# connectors.net
KiCad netlist of a schematic drawn in Altium Designer
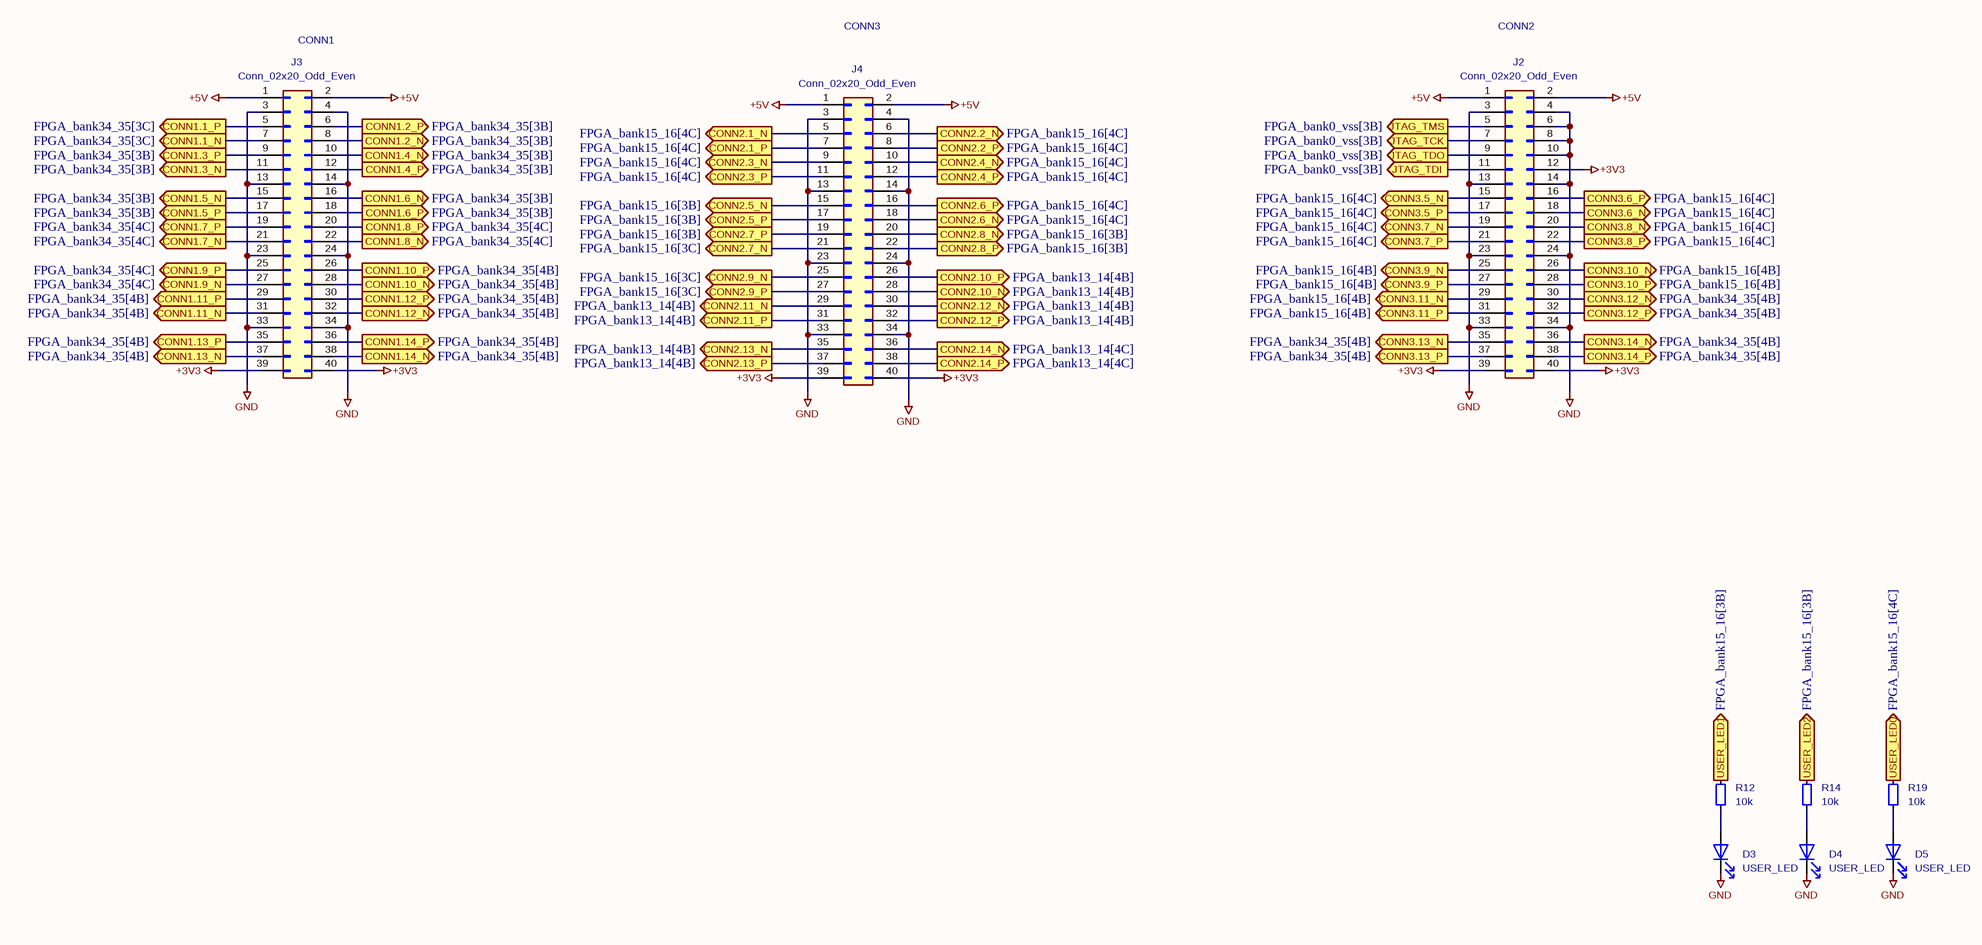
[diagram p0: connectors.SchDoc]

(export (version "E")
  (design (tool "Eeschema 10.0.6"))
  (components
    (comp (ref "D3") (value "USER_LED") (libsource (lib "Device") (part "LED")))
    (comp (ref "D4") (value "USER_LED") (libsource (lib "Device") (part "LED")))
    (comp (ref "D5") (value "USER_LED") (libsource (lib "Device") (part "LED")))
    (comp (ref "J2")
      (value "Conn_02x20_Odd_Even")
      (libsource (lib "Connector_Generic") (part "Conn_02x20_Odd_Even"))
    )
    (comp (ref "J3")
      (value "Conn_02x20_Odd_Even")
      (libsource (lib "Connector_Generic") (part "Conn_02x20_Odd_Even"))
    )
    (comp (ref "J4")
      (value "Conn_02x20_Odd_Even")
      (libsource (lib "Connector_Generic") (part "Conn_02x20_Odd_Even"))
    )
    (comp (ref "R12") (value "10k") (libsource (lib "Device") (part "R_Small")))
    (comp (ref "R14") (value "10k") (libsource (lib "Device") (part "R_Small")))
    (comp (ref "R19") (value "10k") (libsource (lib "Device") (part "R_Small")))
  )
  (nets
    (net (code "1") (name "+3V3") (class "Default")
      (node (ref "J2") (pin "12") (pinfunction "Pin_12_12") (pintype "passive"))
      (node (ref "J2") (pin "39") (pinfunction "Pin_39_39") (pintype "passive"))
      (node (ref "J2") (pin "40") (pinfunction "Pin_40_40") (pintype "passive"))
      (node (ref "J3") (pin "39") (pinfunction "Pin_39_39") (pintype "passive"))
      (node (ref "J3") (pin "40") (pinfunction "Pin_40_40") (pintype "passive"))
      (node (ref "J4") (pin "39") (pinfunction "Pin_39_39") (pintype "passive"))
      (node (ref "J4") (pin "40") (pinfunction "Pin_40_40") (pintype "passive"))
    )
    (net (code "2") (name "+5V") (class "Default")
      (node (ref "J2") (pin "1") (pinfunction "Pin_1_1") (pintype "passive"))
      (node (ref "J2") (pin "2") (pinfunction "Pin_2_2") (pintype "passive"))
      (node (ref "J3") (pin "1") (pinfunction "Pin_1_1") (pintype "passive"))
      (node (ref "J3") (pin "2") (pinfunction "Pin_2_2") (pintype "passive"))
      (node (ref "J4") (pin "1") (pinfunction "Pin_1_1") (pintype "passive"))
      (node (ref "J4") (pin "2") (pinfunction "Pin_2_2") (pintype "passive"))
    )
    (net (code "3") (name "/CONN1.1_N") (class "Default")
      (node (ref "J3") (pin "7") (pinfunction "Pin_7_7") (pintype "passive"))
    )
    (net (code "4") (name "/CONN1.1_P") (class "Default")
      (node (ref "J3") (pin "5") (pinfunction "Pin_5_5") (pintype "passive"))
    )
    (net (code "5") (name "/CONN1.2_N") (class "Default")
      (node (ref "J3") (pin "8") (pinfunction "Pin_8_8") (pintype "passive"))
    )
    (net (code "6") (name "/CONN1.2_P") (class "Default")
      (node (ref "J3") (pin "6") (pinfunction "Pin_6_6") (pintype "passive"))
    )
    (net (code "7") (name "/CONN1.3_N") (class "Default")
      (node (ref "J3") (pin "11") (pinfunction "Pin_11_11") (pintype "passive"))
    )
    (net (code "8") (name "/CONN1.3_P") (class "Default")
      (node (ref "J3") (pin "9") (pinfunction "Pin_9_9") (pintype "passive"))
    )
    (net (code "9") (name "/CONN1.4_N") (class "Default")
      (node (ref "J3") (pin "10") (pinfunction "Pin_10_10") (pintype "passive"))
    )
    (net (code "10") (name "/CONN1.4_P") (class "Default")
      (node (ref "J3") (pin "12") (pinfunction "Pin_12_12") (pintype "passive"))
    )
    (net (code "11") (name "/CONN1.5_N") (class "Default")
      (node (ref "J3") (pin "15") (pinfunction "Pin_15_15") (pintype "passive"))
    )
    (net (code "12") (name "/CONN1.5_P") (class "Default")
      (node (ref "J3") (pin "17") (pinfunction "Pin_17_17") (pintype "passive"))
    )
    (net (code "13") (name "/CONN1.6_N") (class "Default")
      (node (ref "J3") (pin "16") (pinfunction "Pin_16_16") (pintype "passive"))
    )
    (net (code "14") (name "/CONN1.6_P") (class "Default")
      (node (ref "J3") (pin "18") (pinfunction "Pin_18_18") (pintype "passive"))
    )
    (net (code "15") (name "/CONN1.7_N") (class "Default")
      (node (ref "J3") (pin "21") (pinfunction "Pin_21_21") (pintype "passive"))
    )
    (net (code "16") (name "/CONN1.7_P") (class "Default")
      (node (ref "J3") (pin "19") (pinfunction "Pin_19_19") (pintype "passive"))
    )
    (net (code "17") (name "/CONN1.8_N") (class "Default")
      (node (ref "J3") (pin "22") (pinfunction "Pin_22_22") (pintype "passive"))
    )
    (net (code "18") (name "/CONN1.8_P") (class "Default")
      (node (ref "J3") (pin "20") (pinfunction "Pin_20_20") (pintype "passive"))
    )
    (net (code "19") (name "/CONN1.9_N") (class "Default")
      (node (ref "J3") (pin "27") (pinfunction "Pin_27_27") (pintype "passive"))
    )
    (net (code "20") (name "/CONN1.9_P") (class "Default")
      (node (ref "J3") (pin "25") (pinfunction "Pin_25_25") (pintype "passive"))
    )
    (net (code "21") (name "/CONN1.10_N") (class "Default")
      (node (ref "J3") (pin "28") (pinfunction "Pin_28_28") (pintype "passive"))
    )
    (net (code "22") (name "/CONN1.10_P") (class "Default")
      (node (ref "J3") (pin "26") (pinfunction "Pin_26_26") (pintype "passive"))
    )
    (net (code "23") (name "/CONN1.11_N") (class "Default")
      (node (ref "J3") (pin "31") (pinfunction "Pin_31_31") (pintype "passive"))
    )
    (net (code "24") (name "/CONN1.11_P") (class "Default")
      (node (ref "J3") (pin "29") (pinfunction "Pin_29_29") (pintype "passive"))
    )
    (net (code "25") (name "/CONN1.12_N") (class "Default")
      (node (ref "J3") (pin "32") (pinfunction "Pin_32_32") (pintype "passive"))
    )
    (net (code "26") (name "/CONN1.12_P") (class "Default")
      (node (ref "J3") (pin "30") (pinfunction "Pin_30_30") (pintype "passive"))
    )
    (net (code "27") (name "/CONN1.13_N") (class "Default")
      (node (ref "J3") (pin "37") (pinfunction "Pin_37_37") (pintype "passive"))
    )
    (net (code "28") (name "/CONN1.13_P") (class "Default")
      (node (ref "J3") (pin "35") (pinfunction "Pin_35_35") (pintype "passive"))
    )
    (net (code "29") (name "/CONN1.14_N") (class "Default")
      (node (ref "J3") (pin "38") (pinfunction "Pin_38_38") (pintype "passive"))
    )
    (net (code "30") (name "/CONN1.14_P") (class "Default")
      (node (ref "J3") (pin "36") (pinfunction "Pin_36_36") (pintype "passive"))
    )
    (net (code "31") (name "/CONN2.1_N") (class "Default")
      (node (ref "J4") (pin "5") (pinfunction "Pin_5_5") (pintype "passive"))
    )
    (net (code "32") (name "/CONN2.1_P") (class "Default")
      (node (ref "J4") (pin "7") (pinfunction "Pin_7_7") (pintype "passive"))
    )
    (net (code "33") (name "/CONN2.2_N") (class "Default")
      (node (ref "J4") (pin "6") (pinfunction "Pin_6_6") (pintype "passive"))
    )
    (net (code "34") (name "/CONN2.2_P") (class "Default")
      (node (ref "J4") (pin "8") (pinfunction "Pin_8_8") (pintype "passive"))
    )
    (net (code "35") (name "/CONN2.3_N") (class "Default")
      (node (ref "J4") (pin "9") (pinfunction "Pin_9_9") (pintype "passive"))
    )
    (net (code "36") (name "/CONN2.3_P") (class "Default")
      (node (ref "J4") (pin "11") (pinfunction "Pin_11_11") (pintype "passive"))
    )
    (net (code "37") (name "/CONN2.4_N") (class "Default")
      (node (ref "J4") (pin "10") (pinfunction "Pin_10_10") (pintype "passive"))
    )
    (net (code "38") (name "/CONN2.4_P") (class "Default")
      (node (ref "J4") (pin "12") (pinfunction "Pin_12_12") (pintype "passive"))
    )
    (net (code "39") (name "/CONN2.5_N") (class "Default")
      (node (ref "J4") (pin "15") (pinfunction "Pin_15_15") (pintype "passive"))
    )
    (net (code "40") (name "/CONN2.5_P") (class "Default")
      (node (ref "J4") (pin "17") (pinfunction "Pin_17_17") (pintype "passive"))
    )
    (net (code "41") (name "/CONN2.6_N") (class "Default")
      (node (ref "J4") (pin "18") (pinfunction "Pin_18_18") (pintype "passive"))
    )
    (net (code "42") (name "/CONN2.6_P") (class "Default")
      (node (ref "J4") (pin "16") (pinfunction "Pin_16_16") (pintype "passive"))
    )
    (net (code "43") (name "/CONN2.7_N") (class "Default")
      (node (ref "J4") (pin "21") (pinfunction "Pin_21_21") (pintype "passive"))
    )
    (net (code "44") (name "/CONN2.7_P") (class "Default")
      (node (ref "J4") (pin "19") (pinfunction "Pin_19_19") (pintype "passive"))
    )
    (net (code "45") (name "/CONN2.8_N") (class "Default")
      (node (ref "J4") (pin "20") (pinfunction "Pin_20_20") (pintype "passive"))
    )
    (net (code "46") (name "/CONN2.8_P") (class "Default")
      (node (ref "J4") (pin "22") (pinfunction "Pin_22_22") (pintype "passive"))
    )
    (net (code "47") (name "/CONN2.9_N") (class "Default")
      (node (ref "J4") (pin "25") (pinfunction "Pin_25_25") (pintype "passive"))
    )
    (net (code "48") (name "/CONN2.9_P") (class "Default")
      (node (ref "J4") (pin "27") (pinfunction "Pin_27_27") (pintype "passive"))
    )
    (net (code "49") (name "/CONN2.10_N") (class "Default")
      (node (ref "J4") (pin "28") (pinfunction "Pin_28_28") (pintype "passive"))
    )
    (net (code "50") (name "/CONN2.10_P") (class "Default")
      (node (ref "J4") (pin "26") (pinfunction "Pin_26_26") (pintype "passive"))
    )
    (net (code "51") (name "/CONN2.11_N") (class "Default")
      (node (ref "J4") (pin "29") (pinfunction "Pin_29_29") (pintype "passive"))
    )
    (net (code "52") (name "/CONN2.11_P") (class "Default")
      (node (ref "J4") (pin "31") (pinfunction "Pin_31_31") (pintype "passive"))
    )
    (net (code "53") (name "/CONN2.12_N") (class "Default")
      (node (ref "J4") (pin "30") (pinfunction "Pin_30_30") (pintype "passive"))
    )
    (net (code "54") (name "/CONN2.12_P") (class "Default")
      (node (ref "J4") (pin "32") (pinfunction "Pin_32_32") (pintype "passive"))
    )
    (net (code "55") (name "/CONN2.13_N") (class "Default")
      (node (ref "J4") (pin "35") (pinfunction "Pin_35_35") (pintype "passive"))
    )
    (net (code "56") (name "/CONN2.13_P") (class "Default")
      (node (ref "J4") (pin "37") (pinfunction "Pin_37_37") (pintype "passive"))
    )
    (net (code "57") (name "/CONN2.14_N") (class "Default")
      (node (ref "J4") (pin "36") (pinfunction "Pin_36_36") (pintype "passive"))
    )
    (net (code "58") (name "/CONN2.14_P") (class "Default")
      (node (ref "J4") (pin "38") (pinfunction "Pin_38_38") (pintype "passive"))
    )
    (net (code "59") (name "/CONN3.5_N") (class "Default")
      (node (ref "J2") (pin "15") (pinfunction "Pin_15_15") (pintype "passive"))
    )
    (net (code "60") (name "/CONN3.5_P") (class "Default")
      (node (ref "J2") (pin "17") (pinfunction "Pin_17_17") (pintype "passive"))
    )
    (net (code "61") (name "/CONN3.6_N") (class "Default")
      (node (ref "J2") (pin "18") (pinfunction "Pin_18_18") (pintype "passive"))
    )
    (net (code "62") (name "/CONN3.6_P") (class "Default")
      (node (ref "J2") (pin "16") (pinfunction "Pin_16_16") (pintype "passive"))
    )
    (net (code "63") (name "/CONN3.7_N") (class "Default")
      (node (ref "J2") (pin "19") (pinfunction "Pin_19_19") (pintype "passive"))
    )
    (net (code "64") (name "/CONN3.7_P") (class "Default")
      (node (ref "J2") (pin "21") (pinfunction "Pin_21_21") (pintype "passive"))
    )
    (net (code "65") (name "/CONN3.8_N") (class "Default")
      (node (ref "J2") (pin "20") (pinfunction "Pin_20_20") (pintype "passive"))
    )
    (net (code "66") (name "/CONN3.8_P") (class "Default")
      (node (ref "J2") (pin "22") (pinfunction "Pin_22_22") (pintype "passive"))
    )
    (net (code "67") (name "/CONN3.9_N") (class "Default")
      (node (ref "J2") (pin "25") (pinfunction "Pin_25_25") (pintype "passive"))
    )
    (net (code "68") (name "/CONN3.9_P") (class "Default")
      (node (ref "J2") (pin "27") (pinfunction "Pin_27_27") (pintype "passive"))
    )
    (net (code "69") (name "/CONN3.10_N") (class "Default")
      (node (ref "J2") (pin "26") (pinfunction "Pin_26_26") (pintype "passive"))
    )
    (net (code "70") (name "/CONN3.10_P") (class "Default")
      (node (ref "J2") (pin "28") (pinfunction "Pin_28_28") (pintype "passive"))
    )
    (net (code "71") (name "/CONN3.11_N") (class "Default")
      (node (ref "J2") (pin "29") (pinfunction "Pin_29_29") (pintype "passive"))
    )
    (net (code "72") (name "/CONN3.11_P") (class "Default")
      (node (ref "J2") (pin "31") (pinfunction "Pin_31_31") (pintype "passive"))
    )
    (net (code "73") (name "/CONN3.12_N") (class "Default")
      (node (ref "J2") (pin "30") (pinfunction "Pin_30_30") (pintype "passive"))
    )
    (net (code "74") (name "/CONN3.12_P") (class "Default")
      (node (ref "J2") (pin "32") (pinfunction "Pin_32_32") (pintype "passive"))
    )
    (net (code "75") (name "/CONN3.13_N") (class "Default")
      (node (ref "J2") (pin "35") (pinfunction "Pin_35_35") (pintype "passive"))
    )
    (net (code "76") (name "/CONN3.13_P") (class "Default")
      (node (ref "J2") (pin "37") (pinfunction "Pin_37_37") (pintype "passive"))
    )
    (net (code "77") (name "/CONN3.14_N") (class "Default")
      (node (ref "J2") (pin "36") (pinfunction "Pin_36_36") (pintype "passive"))
    )
    (net (code "78") (name "/CONN3.14_P") (class "Default")
      (node (ref "J2") (pin "38") (pinfunction "Pin_38_38") (pintype "passive"))
    )
    (net (code "79") (name "/JTAG_TCK") (class "Default")
      (node (ref "J2") (pin "7") (pinfunction "Pin_7_7") (pintype "passive"))
    )
    (net (code "80") (name "/JTAG_TDI") (class "Default")
      (node (ref "J2") (pin "11") (pinfunction "Pin_11_11") (pintype "passive"))
    )
    (net (code "81") (name "/JTAG_TDO") (class "Default")
      (node (ref "J2") (pin "9") (pinfunction "Pin_9_9") (pintype "passive"))
    )
    (net (code "82") (name "/JTAG_TMS") (class "Default")
      (node (ref "J2") (pin "5") (pinfunction "Pin_5_5") (pintype "passive"))
    )
    (net (code "83") (name "/USER_LED0") (class "Default")
      (node (ref "R19") (pin "1") (pinfunction "1_1") (pintype "passive"))
    )
    (net (code "84") (name "/USER_LED1") (class "Default")
      (node (ref "R12") (pin "1") (pinfunction "1_1") (pintype "passive"))
    )
    (net (code "85") (name "/USER_LED2") (class "Default")
      (node (ref "R14") (pin "1") (pinfunction "1_1") (pintype "passive"))
    )
    (net (code "86") (name "GND") (class "Default")
      (node (ref "D3") (pin "1") (pinfunction "K_1") (pintype "passive"))
      (node (ref "D4") (pin "1") (pinfunction "K_1") (pintype "passive"))
      (node (ref "D5") (pin "1") (pinfunction "K_1") (pintype "passive"))
      (node (ref "J2") (pin "10") (pinfunction "Pin_10_10") (pintype "passive"))
      (node (ref "J2") (pin "13") (pinfunction "Pin_13_13") (pintype "passive"))
      (node (ref "J2") (pin "14") (pinfunction "Pin_14_14") (pintype "passive"))
      (node (ref "J2") (pin "23") (pinfunction "Pin_23_23") (pintype "passive"))
      (node (ref "J2") (pin "24") (pinfunction "Pin_24_24") (pintype "passive"))
      (node (ref "J2") (pin "3") (pinfunction "Pin_3_3") (pintype "passive"))
      (node (ref "J2") (pin "33") (pinfunction "Pin_33_33") (pintype "passive"))
      (node (ref "J2") (pin "34") (pinfunction "Pin_34_34") (pintype "passive"))
      (node (ref "J2") (pin "4") (pinfunction "Pin_4_4") (pintype "passive"))
      (node (ref "J2") (pin "6") (pinfunction "Pin_6_6") (pintype "passive"))
      (node (ref "J2") (pin "8") (pinfunction "Pin_8_8") (pintype "passive"))
      (node (ref "J3") (pin "13") (pinfunction "Pin_13_13") (pintype "passive"))
      (node (ref "J3") (pin "14") (pinfunction "Pin_14_14") (pintype "passive"))
      (node (ref "J3") (pin "23") (pinfunction "Pin_23_23") (pintype "passive"))
      (node (ref "J3") (pin "24") (pinfunction "Pin_24_24") (pintype "passive"))
      (node (ref "J3") (pin "3") (pinfunction "Pin_3_3") (pintype "passive"))
      (node (ref "J3") (pin "33") (pinfunction "Pin_33_33") (pintype "passive"))
      (node (ref "J3") (pin "34") (pinfunction "Pin_34_34") (pintype "passive"))
      (node (ref "J3") (pin "4") (pinfunction "Pin_4_4") (pintype "passive"))
      (node (ref "J4") (pin "13") (pinfunction "Pin_13_13") (pintype "passive"))
      (node (ref "J4") (pin "14") (pinfunction "Pin_14_14") (pintype "passive"))
      (node (ref "J4") (pin "23") (pinfunction "Pin_23_23") (pintype "passive"))
      (node (ref "J4") (pin "24") (pinfunction "Pin_24_24") (pintype "passive"))
      (node (ref "J4") (pin "3") (pinfunction "Pin_3_3") (pintype "passive"))
      (node (ref "J4") (pin "33") (pinfunction "Pin_33_33") (pintype "passive"))
      (node (ref "J4") (pin "34") (pinfunction "Pin_34_34") (pintype "passive"))
      (node (ref "J4") (pin "4") (pinfunction "Pin_4_4") (pintype "passive"))
    )
    (net (code "87") (name "Net-(D3-A)") (class "Default")
      (node (ref "D3") (pin "2") (pinfunction "A_2") (pintype "passive"))
      (node (ref "R12") (pin "2") (pinfunction "2_2") (pintype "passive"))
    )
    (net (code "88") (name "Net-(D4-A)") (class "Default")
      (node (ref "D4") (pin "2") (pinfunction "A_2") (pintype "passive"))
      (node (ref "R14") (pin "2") (pinfunction "2_2") (pintype "passive"))
    )
    (net (code "89") (name "Net-(D5-A)") (class "Default")
      (node (ref "D5") (pin "2") (pinfunction "A_2") (pintype "passive"))
      (node (ref "R19") (pin "2") (pinfunction "2_2") (pintype "passive"))
    )
  )
)
